# hermesONE_Mini.net
KiCad netlist of a schematic drawn in EAGLE
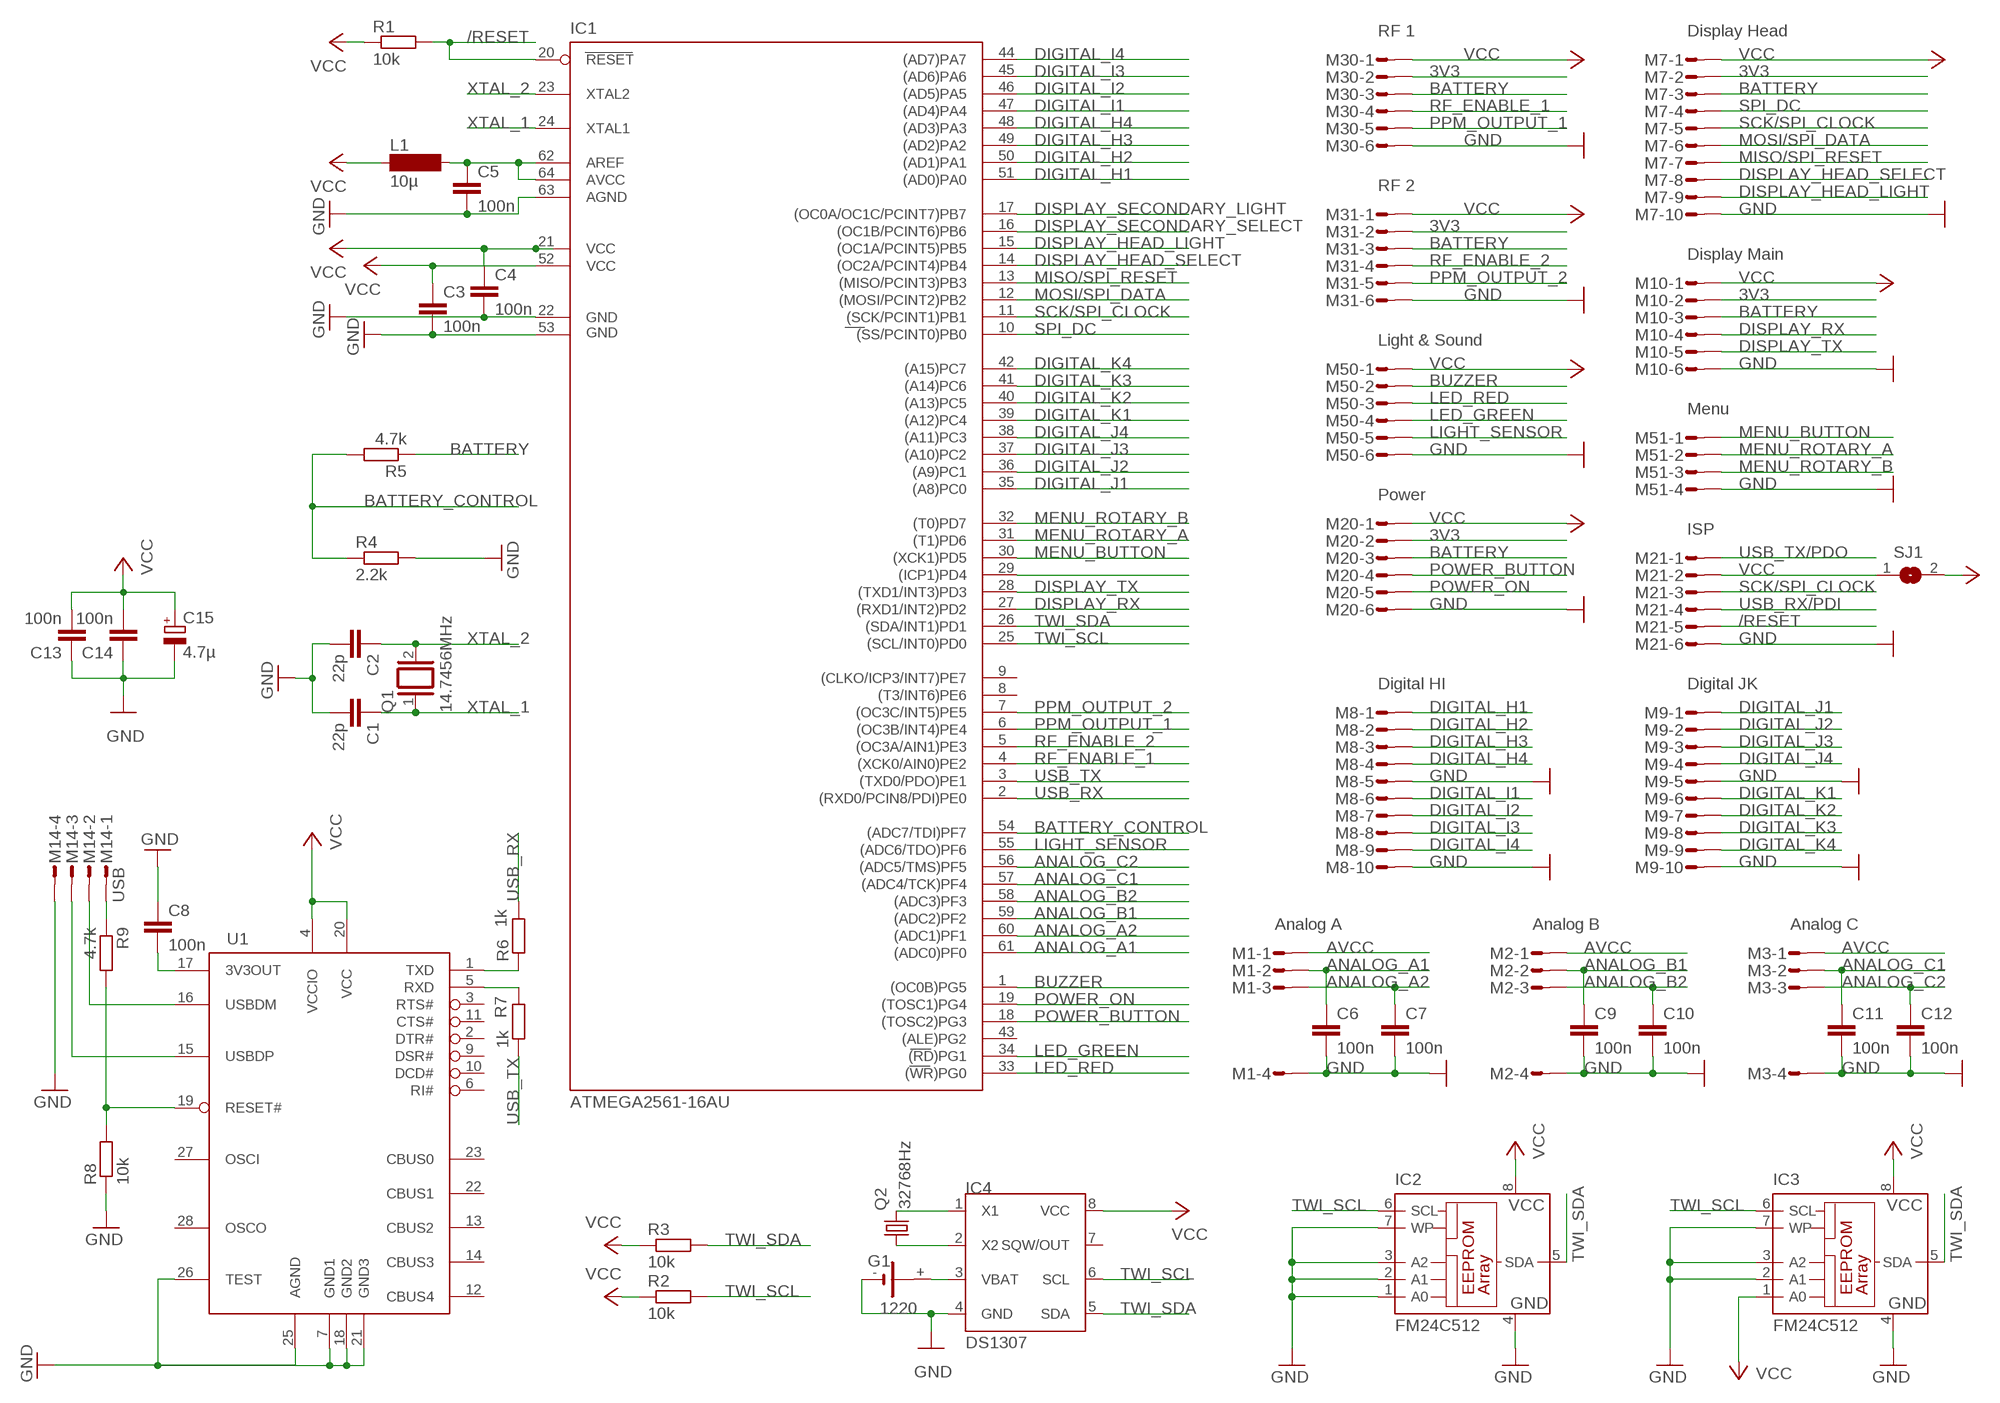
[diagram p0: schematic, sheet 1]

(export (version "E")
  (design (tool "Eeschema 10.0.6"))
  (components
    (comp (ref "C1")
      (value "22p")
      (footprint "eagle-import:C0603")
      (libsource (lib "eagle-import") (part "C-EUC0603"))
    )
    (comp (ref "C2")
      (value "22p")
      (footprint "eagle-import:C0603")
      (libsource (lib "eagle-import") (part "C-EUC0603"))
    )
    (comp (ref "C3")
      (value "100n")
      (footprint "eagle-import:C0603")
      (libsource (lib "eagle-import") (part "C-EUC0603"))
    )
    (comp (ref "C4")
      (value "100n")
      (footprint "eagle-import:C0603")
      (libsource (lib "eagle-import") (part "C-EUC0603"))
    )
    (comp (ref "C5")
      (value "100n")
      (footprint "eagle-import:C0603")
      (libsource (lib "eagle-import") (part "C-EUC0603"))
    )
    (comp (ref "C6")
      (value "100n")
      (footprint "eagle-import:C0603")
      (libsource (lib "eagle-import") (part "C-EUC0603"))
    )
    (comp (ref "C7")
      (value "100n")
      (footprint "eagle-import:C0603")
      (libsource (lib "eagle-import") (part "C-EUC0603"))
    )
    (comp (ref "C8")
      (value "100n")
      (footprint "eagle-import:C0603")
      (libsource (lib "eagle-import") (part "C-EUC0603"))
    )
    (comp (ref "C9")
      (value "100n")
      (footprint "eagle-import:C0603")
      (libsource (lib "eagle-import") (part "C-EUC0603"))
    )
    (comp (ref "C10")
      (value "100n")
      (footprint "eagle-import:C0603")
      (libsource (lib "eagle-import") (part "C-EUC0603"))
    )
    (comp (ref "C11")
      (value "100n")
      (footprint "eagle-import:C0603")
      (libsource (lib "eagle-import") (part "C-EUC0603"))
    )
    (comp (ref "C12")
      (value "100n")
      (footprint "eagle-import:C0603")
      (libsource (lib "eagle-import") (part "C-EUC0603"))
    )
    (comp (ref "C13")
      (value "100n")
      (footprint "eagle-import:C0603")
      (libsource (lib "eagle-import") (part "C-EUC0603"))
    )
    (comp (ref "C14")
      (value "100n")
      (footprint "eagle-import:C0603")
      (libsource (lib "eagle-import") (part "C-EUC0603"))
    )
    (comp (ref "C15")
      (value "4.7µ")
      (footprint "eagle-import:PANASONIC_B")
      (libsource (lib "eagle-import") (part "CPOL-EUB"))
    )
    (comp (ref "G1")
      (value "1220")
      (footprint "eagle-import:KZH12THM")
      (libsource (lib "eagle-import") (part "1220"))
    )
    (comp (ref "IC1")
      (value "ATMEGA2561-16AU")
      (footprint "eagle-import:TQFP64")
      (libsource (lib "eagle-import") (part "ATMEGA2561AU-16"))
    )
    (comp (ref "IC2")
      (value "FM24C512")
      (footprint "eagle-import:SO-08M")
      (libsource (lib "eagle-import") (part "24SMC64"))
    )
    (comp (ref "IC3")
      (value "FM24C512")
      (footprint "eagle-import:SO-08M")
      (libsource (lib "eagle-import") (part "24SMC64"))
    )
    (comp (ref "IC4")
      (value "DS1307")
      (footprint "eagle-import:SOIC-8")
      (libsource (lib "eagle-import") (part "DS1307"))
    )
    (comp (ref "L1")
      (value "10µ")
      (footprint "eagle-import:SM-1206")
      (libsource (lib "eagle-import") (part "SM-1206"))
    )
    (comp (ref "M1")
      (value "Analog A")
      (footprint "eagle-import:MT-4")
      (fields (field (name "MPN") "7-215079-4"))
      (libsource (lib "eagle-import") (part "MT-4"))
    )
    (comp (ref "M2")
      (value "Analog B")
      (footprint "eagle-import:MT-4")
      (fields (field (name "MPN") "7-215079-4"))
      (libsource (lib "eagle-import") (part "MT-4"))
    )
    (comp (ref "M3")
      (value "Analog C")
      (footprint "eagle-import:MT-4")
      (fields (field (name "MPN") "7-215079-4"))
      (libsource (lib "eagle-import") (part "MT-4"))
    )
    (comp (ref "M7")
      (value "Display Head")
      (footprint "eagle-import:MT-10")
      (fields (field (name "MF") "FARNELL") (field (name "MPN") "8-215079-0"))
      (libsource (lib "eagle-import") (part "MT-10"))
    )
    (comp (ref "M8")
      (value "Digital HI")
      (footprint "eagle-import:MT-10")
      (fields (field (name "MF") "FARNELL") (field (name "MPN") "8-215079-0"))
      (libsource (lib "eagle-import") (part "MT-10"))
    )
    (comp (ref "M9")
      (value "Digital JK")
      (footprint "eagle-import:MT-10")
      (fields (field (name "MF") "FARNELL") (field (name "MPN") "8-215079-0"))
      (libsource (lib "eagle-import") (part "MT-10"))
    )
    (comp (ref "M10")
      (value "Display Main")
      (footprint "eagle-import:MT-6")
      (fields (field (name "MPN") "7-215079-6"))
      (libsource (lib "eagle-import") (part "MT-6"))
    )
    (comp (ref "M14")
      (value "USB")
      (footprint "eagle-import:MT-4")
      (fields (field (name "MPN") "7-215079-4"))
      (libsource (lib "eagle-import") (part "MT-4"))
    )
    (comp (ref "M20")
      (value "Power")
      (footprint "eagle-import:MT-6")
      (fields (field (name "MPN") "7-215079-6"))
      (libsource (lib "eagle-import") (part "MT-6"))
    )
    (comp (ref "M21")
      (value "ISP")
      (footprint "eagle-import:MT-6")
      (fields (field (name "MPN") "7-215079-6"))
      (libsource (lib "eagle-import") (part "MT-6"))
    )
    (comp (ref "M30")
      (value "RF 1")
      (footprint "eagle-import:MT-6")
      (fields (field (name "MPN") "7-215079-6"))
      (libsource (lib "eagle-import") (part "MT-6"))
    )
    (comp (ref "M31")
      (value "RF 2")
      (footprint "eagle-import:MT-6")
      (fields (field (name "MPN") "7-215079-6"))
      (libsource (lib "eagle-import") (part "MT-6"))
    )
    (comp (ref "M50")
      (value "Light & Sound")
      (footprint "eagle-import:MT-6")
      (fields (field (name "MPN") "7-215079-6"))
      (libsource (lib "eagle-import") (part "MT-6"))
    )
    (comp (ref "M51")
      (value "Menu")
      (footprint "eagle-import:MT-4")
      (fields (field (name "MPN") "7-215079-4"))
      (libsource (lib "eagle-import") (part "MT-4"))
    )
    (comp (ref "Q1")
      (value "14.7456MHz")
      (footprint "eagle-import:QS")
      (libsource (lib "eagle-import") (part "XTAL/S"))
    )
    (comp (ref "Q2")
      (value "32768Hz")
      (footprint "eagle-import:TC26H")
      (libsource (lib "eagle-import") (part "CRYSTALTC26H"))
    )
    (comp (ref "R1")
      (value "10k")
      (footprint "eagle-import:R0603")
      (libsource (lib "eagle-import") (part "R-EU_R0603"))
    )
    (comp (ref "R2")
      (value "10k")
      (footprint "eagle-import:R0603")
      (libsource (lib "eagle-import") (part "R-EU_R0603"))
    )
    (comp (ref "R3")
      (value "10k")
      (footprint "eagle-import:R0603")
      (libsource (lib "eagle-import") (part "R-EU_R0603"))
    )
    (comp (ref "R4")
      (value "2.2k")
      (footprint "eagle-import:R0603")
      (libsource (lib "eagle-import") (part "R-EU_R0603"))
    )
    (comp (ref "R5")
      (value "4.7k")
      (footprint "eagle-import:R0603")
      (libsource (lib "eagle-import") (part "R-EU_R0603"))
    )
    (comp (ref "R6")
      (value "1k")
      (footprint "eagle-import:R0603")
      (libsource (lib "eagle-import") (part "R-EU_R0603"))
    )
    (comp (ref "R7")
      (value "1k")
      (footprint "eagle-import:R0603")
      (libsource (lib "eagle-import") (part "R-EU_R0603"))
    )
    (comp (ref "R8")
      (value "10k")
      (footprint "eagle-import:R0603")
      (libsource (lib "eagle-import") (part "R-EU_R0603"))
    )
    (comp (ref "R9")
      (value "4.7k")
      (footprint "eagle-import:R0603")
      (libsource (lib "eagle-import") (part "R-EU_R0603"))
    )
    (comp (ref "SJ1") (value "SJ") (footprint "eagle-import:SJ") (libsource (lib "eagle-import") (part "SJ")))
    (comp (ref "U1")
      (value "FT232RL")
      (footprint "eagle-import:SSOP28DB")
      (libsource (lib "eagle-import") (part "FT232RL"))
    )
  )
  (nets
    (net (code "1") (name "/3V3") (class "Default")
      (node (ref "M10") (pin "2") (pinfunction "S_2") (pintype "passive"))
      (node (ref "M20") (pin "2") (pinfunction "S_2") (pintype "passive"))
      (node (ref "M30") (pin "2") (pinfunction "S_2") (pintype "passive"))
      (node (ref "M31") (pin "2") (pinfunction "S_2") (pintype "passive"))
      (node (ref "M7") (pin "2") (pinfunction "S_2") (pintype "passive"))
    )
    (net (code "2") (name "/ANALOG_A1") (class "Default")
      (node (ref "C6") (pin "1") (pinfunction "1_1") (pintype "passive"))
      (node (ref "IC1") (pin "61") (pinfunction "(ADC0)PF0_61") (pintype "bidirectional"))
      (node (ref "M1") (pin "2") (pinfunction "S_2") (pintype "passive"))
    )
    (net (code "3") (name "/ANALOG_A2") (class "Default")
      (node (ref "C7") (pin "1") (pinfunction "1_1") (pintype "passive"))
      (node (ref "IC1") (pin "60") (pinfunction "(ADC1)PF1_60") (pintype "bidirectional"))
      (node (ref "M1") (pin "3") (pinfunction "S_3") (pintype "passive"))
    )
    (net (code "4") (name "/ANALOG_B1") (class "Default")
      (node (ref "C9") (pin "1") (pinfunction "1_1") (pintype "passive"))
      (node (ref "IC1") (pin "59") (pinfunction "(ADC2)PF2_59") (pintype "bidirectional"))
      (node (ref "M2") (pin "2") (pinfunction "S_2") (pintype "passive"))
    )
    (net (code "5") (name "/ANALOG_B2") (class "Default")
      (node (ref "C10") (pin "1") (pinfunction "1_1") (pintype "passive"))
      (node (ref "IC1") (pin "58") (pinfunction "(ADC3)PF3_58") (pintype "bidirectional"))
      (node (ref "M2") (pin "3") (pinfunction "S_3") (pintype "passive"))
    )
    (net (code "6") (name "/ANALOG_C1") (class "Default")
      (node (ref "C11") (pin "1") (pinfunction "1_1") (pintype "passive"))
      (node (ref "IC1") (pin "57") (pinfunction "(ADC4/TCK)PF4_57") (pintype "bidirectional"))
      (node (ref "M3") (pin "2") (pinfunction "S_2") (pintype "passive"))
    )
    (net (code "7") (name "/ANALOG_C2") (class "Default")
      (node (ref "C12") (pin "1") (pinfunction "1_1") (pintype "passive"))
      (node (ref "IC1") (pin "56") (pinfunction "(ADC5/TMS)PF5_56") (pintype "bidirectional"))
      (node (ref "M3") (pin "3") (pinfunction "S_3") (pintype "passive"))
    )
    (net (code "8") (name "/AVCC") (class "Default")
      (node (ref "M1") (pin "1") (pinfunction "S_1") (pintype "passive"))
      (node (ref "M2") (pin "1") (pinfunction "S_1") (pintype "passive"))
      (node (ref "M3") (pin "1") (pinfunction "S_1") (pintype "passive"))
    )
    (net (code "9") (name "/BATTERY") (class "Default")
      (node (ref "M10") (pin "3") (pinfunction "S_3") (pintype "passive"))
      (node (ref "M20") (pin "3") (pinfunction "S_3") (pintype "passive"))
      (node (ref "M30") (pin "3") (pinfunction "S_3") (pintype "passive"))
      (node (ref "M31") (pin "3") (pinfunction "S_3") (pintype "passive"))
      (node (ref "M7") (pin "3") (pinfunction "S_3") (pintype "passive"))
      (node (ref "R5") (pin "1") (pinfunction "1_1") (pintype "passive"))
    )
    (net (code "10") (name "/BATTERY_CONTROL") (class "Default")
      (node (ref "IC1") (pin "54") (pinfunction "(ADC7/TDI)PF7_54") (pintype "bidirectional"))
      (node (ref "R4") (pin "1") (pinfunction "1_1") (pintype "passive"))
      (node (ref "R5") (pin "2") (pinfunction "2_2") (pintype "passive"))
    )
    (net (code "11") (name "/BUZZER") (class "Default")
      (node (ref "IC1") (pin "1") (pinfunction "(OC0B)PG5_1") (pintype "bidirectional"))
      (node (ref "M50") (pin "2") (pinfunction "S_2") (pintype "passive"))
    )
    (net (code "12") (name "/DIGITAL_H1") (class "Default")
      (node (ref "IC1") (pin "51") (pinfunction "(AD0)PA0_51") (pintype "bidirectional"))
      (node (ref "M8") (pin "1") (pinfunction "S_1") (pintype "passive"))
    )
    (net (code "13") (name "/DIGITAL_H2") (class "Default")
      (node (ref "IC1") (pin "50") (pinfunction "(AD1)PA1_50") (pintype "bidirectional"))
      (node (ref "M8") (pin "2") (pinfunction "S_2") (pintype "passive"))
    )
    (net (code "14") (name "/DIGITAL_H3") (class "Default")
      (node (ref "IC1") (pin "49") (pinfunction "(AD2)PA2_49") (pintype "bidirectional"))
      (node (ref "M8") (pin "3") (pinfunction "S_3") (pintype "passive"))
    )
    (net (code "15") (name "/DIGITAL_H4") (class "Default")
      (node (ref "IC1") (pin "48") (pinfunction "(AD3)PA3_48") (pintype "bidirectional"))
      (node (ref "M8") (pin "4") (pinfunction "S_4") (pintype "passive"))
    )
    (net (code "16") (name "/DIGITAL_I1") (class "Default")
      (node (ref "IC1") (pin "47") (pinfunction "(AD4)PA4_47") (pintype "bidirectional"))
      (node (ref "M8") (pin "6") (pinfunction "S_6") (pintype "passive"))
    )
    (net (code "17") (name "/DIGITAL_I2") (class "Default")
      (node (ref "IC1") (pin "46") (pinfunction "(AD5)PA5_46") (pintype "bidirectional"))
      (node (ref "M8") (pin "7") (pinfunction "S_7") (pintype "passive"))
    )
    (net (code "18") (name "/DIGITAL_I3") (class "Default")
      (node (ref "IC1") (pin "45") (pinfunction "(AD6)PA6_45") (pintype "bidirectional"))
      (node (ref "M8") (pin "8") (pinfunction "S_8") (pintype "passive"))
    )
    (net (code "19") (name "/DIGITAL_I4") (class "Default")
      (node (ref "IC1") (pin "44") (pinfunction "(AD7)PA7_44") (pintype "bidirectional"))
      (node (ref "M8") (pin "9") (pinfunction "S_9") (pintype "passive"))
    )
    (net (code "20") (name "/DIGITAL_J1") (class "Default")
      (node (ref "IC1") (pin "35") (pinfunction "(A8)PC0_35") (pintype "bidirectional"))
      (node (ref "M9") (pin "1") (pinfunction "S_1") (pintype "passive"))
    )
    (net (code "21") (name "/DIGITAL_J2") (class "Default")
      (node (ref "IC1") (pin "36") (pinfunction "(A9)PC1_36") (pintype "bidirectional"))
      (node (ref "M9") (pin "2") (pinfunction "S_2") (pintype "passive"))
    )
    (net (code "22") (name "/DIGITAL_J3") (class "Default")
      (node (ref "IC1") (pin "37") (pinfunction "(A10)PC2_37") (pintype "bidirectional"))
      (node (ref "M9") (pin "3") (pinfunction "S_3") (pintype "passive"))
    )
    (net (code "23") (name "/DIGITAL_J4") (class "Default")
      (node (ref "IC1") (pin "38") (pinfunction "(A11)PC3_38") (pintype "bidirectional"))
      (node (ref "M9") (pin "4") (pinfunction "S_4") (pintype "passive"))
    )
    (net (code "24") (name "/DIGITAL_K1") (class "Default")
      (node (ref "IC1") (pin "39") (pinfunction "(A12)PC4_39") (pintype "bidirectional"))
      (node (ref "M9") (pin "6") (pinfunction "S_6") (pintype "passive"))
    )
    (net (code "25") (name "/DIGITAL_K2") (class "Default")
      (node (ref "IC1") (pin "40") (pinfunction "(A13)PC5_40") (pintype "bidirectional"))
      (node (ref "M9") (pin "7") (pinfunction "S_7") (pintype "passive"))
    )
    (net (code "26") (name "/DIGITAL_K3") (class "Default")
      (node (ref "IC1") (pin "41") (pinfunction "(A14)PC6_41") (pintype "bidirectional"))
      (node (ref "M9") (pin "8") (pinfunction "S_8") (pintype "passive"))
    )
    (net (code "27") (name "/DIGITAL_K4") (class "Default")
      (node (ref "IC1") (pin "42") (pinfunction "(A15)PC7_42") (pintype "bidirectional"))
      (node (ref "M9") (pin "9") (pinfunction "S_9") (pintype "passive"))
    )
    (net (code "28") (name "/DISPLAY_HEAD_LIGHT") (class "Default")
      (node (ref "IC1") (pin "15") (pinfunction "(OC1A/PCINT5)PB5_15") (pintype "bidirectional"))
      (node (ref "M7") (pin "9") (pinfunction "S_9") (pintype "passive"))
    )
    (net (code "29") (name "/DISPLAY_HEAD_SELECT") (class "Default")
      (node (ref "IC1") (pin "14") (pinfunction "(OC2A/PCINT4)PB4_14") (pintype "bidirectional"))
      (node (ref "M7") (pin "8") (pinfunction "S_8") (pintype "passive"))
    )
    (net (code "30") (name "/DISPLAY_RX") (class "Default")
      (node (ref "IC1") (pin "27") (pinfunction "(RXD1/INT2)PD2_27") (pintype "bidirectional"))
      (node (ref "M10") (pin "4") (pinfunction "S_4") (pintype "passive"))
    )
    (net (code "31") (name "/DISPLAY_SECONDARY_LIGHT") (class "Default")
      (node (ref "IC1") (pin "17") (pinfunction "(OC0A/OC1C/PCINT7)PB7_17") (pintype "bidirectional"))
    )
    (net (code "32") (name "/DISPLAY_SECONDARY_SELECT") (class "Default")
      (node (ref "IC1") (pin "16") (pinfunction "(OC1B/PCINT6)PB6_16") (pintype "bidirectional"))
    )
    (net (code "33") (name "/DISPLAY_TX") (class "Default")
      (node (ref "IC1") (pin "28") (pinfunction "(TXD1/INT3)PD3_28") (pintype "bidirectional"))
      (node (ref "M10") (pin "5") (pinfunction "S_5") (pintype "passive"))
    )
    (net (code "34") (name "/LED_GREEN") (class "Default")
      (node (ref "IC1") (pin "34") (pinfunction "(RD)PG1_34") (pintype "bidirectional"))
      (node (ref "M50") (pin "4") (pinfunction "S_4") (pintype "passive"))
    )
    (net (code "35") (name "/LED_RED") (class "Default")
      (node (ref "IC1") (pin "33") (pinfunction "(WR)PG0_33") (pintype "bidirectional"))
      (node (ref "M50") (pin "3") (pinfunction "S_3") (pintype "passive"))
    )
    (net (code "36") (name "/LIGHT_SENSOR") (class "Default")
      (node (ref "IC1") (pin "55") (pinfunction "(ADC6/TDO)PF6_55") (pintype "bidirectional"))
      (node (ref "M50") (pin "5") (pinfunction "S_5") (pintype "passive"))
    )
    (net (code "37") (name "/MENU_BUTTON") (class "Default")
      (node (ref "IC1") (pin "30") (pinfunction "(XCK1)PD5_30") (pintype "bidirectional"))
      (node (ref "M51") (pin "1") (pinfunction "S_1") (pintype "passive"))
    )
    (net (code "38") (name "/MENU_ROTARY_A") (class "Default")
      (node (ref "IC1") (pin "31") (pinfunction "(T1)PD6_31") (pintype "bidirectional"))
      (node (ref "M51") (pin "2") (pinfunction "S_2") (pintype "passive"))
    )
    (net (code "39") (name "/MENU_ROTARY_B") (class "Default")
      (node (ref "IC1") (pin "32") (pinfunction "(T0)PD7_32") (pintype "bidirectional"))
      (node (ref "M51") (pin "3") (pinfunction "S_3") (pintype "passive"))
    )
    (net (code "40") (name "/MISO{slash}SPI_RESET") (class "Default")
      (node (ref "IC1") (pin "13") (pinfunction "(MISO/PCINT3)PB3_13") (pintype "bidirectional"))
      (node (ref "M7") (pin "7") (pinfunction "S_7") (pintype "passive"))
    )
    (net (code "41") (name "/MOSI{slash}SPI_DATA") (class "Default")
      (node (ref "IC1") (pin "12") (pinfunction "(MOSI/PCINT2)PB2_12") (pintype "bidirectional"))
      (node (ref "M7") (pin "6") (pinfunction "S_6") (pintype "passive"))
    )
    (net (code "42") (name "/POWER_BUTTON") (class "Default")
      (node (ref "IC1") (pin "18") (pinfunction "(TOSC2)PG3_18") (pintype "bidirectional"))
      (node (ref "M20") (pin "4") (pinfunction "S_4") (pintype "passive"))
    )
    (net (code "43") (name "/POWER_ON") (class "Default")
      (node (ref "IC1") (pin "19") (pinfunction "(TOSC1)PG4_19") (pintype "bidirectional"))
      (node (ref "M20") (pin "5") (pinfunction "S_5") (pintype "passive"))
    )
    (net (code "44") (name "/PPM_OUTPUT_1") (class "Default")
      (node (ref "IC1") (pin "6") (pinfunction "(OC3B/INT4)PE4_6") (pintype "bidirectional"))
      (node (ref "M30") (pin "5") (pinfunction "S_5") (pintype "passive"))
    )
    (net (code "45") (name "/PPM_OUTPUT_2") (class "Default")
      (node (ref "IC1") (pin "7") (pinfunction "(OC3C/INT5)PE5_7") (pintype "bidirectional"))
      (node (ref "M31") (pin "5") (pinfunction "S_5") (pintype "passive"))
    )
    (net (code "46") (name "/RF_ENABLE_1") (class "Default")
      (node (ref "IC1") (pin "4") (pinfunction "(XCK0/AIN0)PE2_4") (pintype "bidirectional"))
      (node (ref "M30") (pin "4") (pinfunction "S_4") (pintype "passive"))
    )
    (net (code "47") (name "/RF_ENABLE_2") (class "Default")
      (node (ref "IC1") (pin "5") (pinfunction "(OC3A/AIN1)PE3_5") (pintype "bidirectional"))
      (node (ref "M31") (pin "4") (pinfunction "S_4") (pintype "passive"))
    )
    (net (code "48") (name "/SCK{slash}SPI_CLOCK") (class "Default")
      (node (ref "IC1") (pin "11") (pinfunction "(SCK/PCINT1)PB1_11") (pintype "bidirectional"))
      (node (ref "M21") (pin "3") (pinfunction "S_3") (pintype "passive"))
      (node (ref "M7") (pin "5") (pinfunction "S_5") (pintype "passive"))
    )
    (net (code "49") (name "/SPI_DC") (class "Default")
      (node (ref "IC1") (pin "10") (pinfunction "(SS/PCINT0)PB0_10") (pintype "bidirectional"))
      (node (ref "M7") (pin "4") (pinfunction "S_4") (pintype "passive"))
    )
    (net (code "50") (name "/TWI_SCL") (class "Default")
      (node (ref "IC1") (pin "25") (pinfunction "(SCL/INT0)PD0_25") (pintype "bidirectional"))
      (node (ref "IC2") (pin "6") (pinfunction "SCL_6") (pintype "input"))
      (node (ref "IC3") (pin "6") (pinfunction "SCL_6") (pintype "input"))
      (node (ref "IC4") (pin "6") (pinfunction "SCL_6") (pintype "input"))
      (node (ref "R2") (pin "2") (pinfunction "2_2") (pintype "passive"))
    )
    (net (code "51") (name "/TWI_SDA") (class "Default")
      (node (ref "IC1") (pin "26") (pinfunction "(SDA/INT1)PD1_26") (pintype "bidirectional"))
      (node (ref "IC2") (pin "5") (pinfunction "SDA_5") (pintype "bidirectional"))
      (node (ref "IC3") (pin "5") (pinfunction "SDA_5") (pintype "bidirectional"))
      (node (ref "IC4") (pin "5") (pinfunction "SDA_5") (pintype "bidirectional"))
      (node (ref "R3") (pin "2") (pinfunction "2_2") (pintype "passive"))
    )
    (net (code "52") (name "/USB_RX") (class "Default")
      (node (ref "IC1") (pin "2") (pinfunction "(RXD0/PCIN8/PDI)PE0_2") (pintype "bidirectional"))
      (node (ref "R6") (pin "2") (pinfunction "2_2") (pintype "passive"))
    )
    (net (code "53") (name "/USB_RX{slash}PDI") (class "Default")
      (node (ref "M21") (pin "4") (pinfunction "S_4") (pintype "passive"))
    )
    (net (code "54") (name "/USB_TX") (class "Default")
      (node (ref "IC1") (pin "3") (pinfunction "(TXD0/PDO)PE1_3") (pintype "bidirectional"))
      (node (ref "R7") (pin "2") (pinfunction "2_2") (pintype "passive"))
    )
    (net (code "55") (name "/USB_TX{slash}PDO") (class "Default")
      (node (ref "M21") (pin "1") (pinfunction "S_1") (pintype "passive"))
    )
    (net (code "56") (name "/XTAL_1") (class "Default")
      (node (ref "C1") (pin "1") (pinfunction "1_1") (pintype "passive"))
      (node (ref "IC1") (pin "24") (pinfunction "XTAL1_24") (pintype "input"))
      (node (ref "Q1") (pin "1") (pinfunction "1_1") (pintype "passive"))
    )
    (net (code "57") (name "/XTAL_2") (class "Default")
      (node (ref "C2") (pin "1") (pinfunction "1_1") (pintype "passive"))
      (node (ref "IC1") (pin "23") (pinfunction "XTAL2_23") (pintype "output"))
      (node (ref "Q1") (pin "2") (pinfunction "2_2") (pintype "passive"))
    )
    (net (code "58") (name "/{slash}RESET") (class "Default")
      (node (ref "IC1") (pin "20") (pinfunction "RESET_20") (pintype "input"))
      (node (ref "M21") (pin "5") (pinfunction "S_5") (pintype "passive"))
      (node (ref "R1") (pin "2") (pinfunction "2_2") (pintype "passive"))
    )
    (net (code "59") (name "GND") (class "Default")
      (node (ref "C1") (pin "2") (pinfunction "2_2") (pintype "passive"))
      (node (ref "C10") (pin "2") (pinfunction "2_2") (pintype "passive"))
      (node (ref "C11") (pin "2") (pinfunction "2_2") (pintype "passive"))
      (node (ref "C12") (pin "2") (pinfunction "2_2") (pintype "passive"))
      (node (ref "C13") (pin "1") (pinfunction "1_1") (pintype "passive"))
      (node (ref "C14") (pin "1") (pinfunction "1_1") (pintype "passive"))
      (node (ref "C15") (pin "-") (pinfunction "-_-") (pintype "passive"))
      (node (ref "C2") (pin "2") (pinfunction "2_2") (pintype "passive"))
      (node (ref "C3") (pin "2") (pinfunction "2_2") (pintype "passive"))
      (node (ref "C4") (pin "2") (pinfunction "2_2") (pintype "passive"))
      (node (ref "C5") (pin "2") (pinfunction "2_2") (pintype "passive"))
      (node (ref "C6") (pin "2") (pinfunction "2_2") (pintype "passive"))
      (node (ref "C7") (pin "2") (pinfunction "2_2") (pintype "passive"))
      (node (ref "C8") (pin "1") (pinfunction "1_1") (pintype "passive"))
      (node (ref "C9") (pin "2") (pinfunction "2_2") (pintype "passive"))
      (node (ref "G1") (pin "-") (pinfunction "-_-") (pintype "passive"))
      (node (ref "IC1") (pin "22") (pinfunction "GND_22") (pintype "power_in"))
      (node (ref "IC1") (pin "53") (pinfunction "GND1_53") (pintype "power_in"))
      (node (ref "IC1") (pin "63") (pinfunction "AGND_63") (pintype "power_in"))
      (node (ref "IC2") (pin "1") (pinfunction "A0_1") (pintype "input"))
      (node (ref "IC2") (pin "2") (pinfunction "A1_2") (pintype "input"))
      (node (ref "IC2") (pin "3") (pinfunction "A2_3") (pintype "input"))
      (node (ref "IC2") (pin "4") (pinfunction "GND_4") (pintype "power_in"))
      (node (ref "IC2") (pin "7") (pinfunction "WP_7") (pintype "input"))
      (node (ref "IC3") (pin "2") (pinfunction "A1_2") (pintype "input"))
      (node (ref "IC3") (pin "3") (pinfunction "A2_3") (pintype "input"))
      (node (ref "IC3") (pin "4") (pinfunction "GND_4") (pintype "power_in"))
      (node (ref "IC3") (pin "7") (pinfunction "WP_7") (pintype "input"))
      (node (ref "IC4") (pin "4") (pinfunction "GND_4") (pintype "power_in"))
      (node (ref "M1") (pin "4") (pinfunction "S_4") (pintype "passive"))
      (node (ref "M10") (pin "6") (pinfunction "S_6") (pintype "passive"))
      (node (ref "M14") (pin "4") (pinfunction "S_4") (pintype "passive"))
      (node (ref "M2") (pin "4") (pinfunction "S_4") (pintype "passive"))
      (node (ref "M20") (pin "6") (pinfunction "S_6") (pintype "passive"))
      (node (ref "M21") (pin "6") (pinfunction "S_6") (pintype "passive"))
      (node (ref "M3") (pin "4") (pinfunction "S_4") (pintype "passive"))
      (node (ref "M30") (pin "6") (pinfunction "S_6") (pintype "passive"))
      (node (ref "M31") (pin "6") (pinfunction "S_6") (pintype "passive"))
      (node (ref "M50") (pin "6") (pinfunction "S_6") (pintype "passive"))
      (node (ref "M51") (pin "4") (pinfunction "S_4") (pintype "passive"))
      (node (ref "M7") (pin "10") (pinfunction "S_10") (pintype "passive"))
      (node (ref "M8") (pin "10") (pinfunction "S_10") (pintype "passive"))
      (node (ref "M8") (pin "5") (pinfunction "S_5") (pintype "passive"))
      (node (ref "M9") (pin "10") (pinfunction "S_10") (pintype "passive"))
      (node (ref "M9") (pin "5") (pinfunction "S_5") (pintype "passive"))
      (node (ref "R4") (pin "2") (pinfunction "2_2") (pintype "passive"))
      (node (ref "R8") (pin "1") (pinfunction "1_1") (pintype "passive"))
      (node (ref "U1") (pin "18") (pinfunction "GND2_18") (pintype "power_in"))
      (node (ref "U1") (pin "21") (pinfunction "GND3_21") (pintype "power_in"))
      (node (ref "U1") (pin "25") (pinfunction "AGND_25") (pintype "power_in"))
      (node (ref "U1") (pin "26") (pinfunction "TEST_26") (pintype "input"))
      (node (ref "U1") (pin "7") (pinfunction "GND1_7") (pintype "power_in"))
    )
    (net (code "60") (name "Net-(IC1-AREF)") (class "Default")
      (node (ref "C5") (pin "1") (pinfunction "1_1") (pintype "passive"))
      (node (ref "IC1") (pin "62") (pinfunction "AREF_62") (pintype "bidirectional"))
      (node (ref "IC1") (pin "64") (pinfunction "AVCC_64") (pintype "power_in"))
      (node (ref "L1") (pin "2") (pinfunction "2_2") (pintype "passive"))
    )
    (net (code "61") (name "Net-(IC4-VBAT)") (class "Default")
      (node (ref "G1") (pin "+") (pinfunction "+_+") (pintype "passive"))
      (node (ref "IC4") (pin "3") (pinfunction "VBAT_3") (pintype "power_in"))
    )
    (net (code "62") (name "Net-(IC4-X1)") (class "Default")
      (node (ref "IC4") (pin "1") (pinfunction "X1_1") (pintype "input"))
      (node (ref "Q2") (pin "2") (pinfunction "2_2") (pintype "passive"))
    )
    (net (code "63") (name "Net-(IC4-X2)") (class "Default")
      (node (ref "IC4") (pin "2") (pinfunction "X2_2") (pintype "output"))
      (node (ref "Q2") (pin "1") (pinfunction "1_1") (pintype "passive"))
    )
    (net (code "64") (name "Net-(M14A-S)") (class "Default")
      (node (ref "M14") (pin "1") (pinfunction "S_1") (pintype "passive"))
      (node (ref "R9") (pin "1") (pinfunction "1_1") (pintype "passive"))
    )
    (net (code "65") (name "Net-(M14B-S)") (class "Default")
      (node (ref "M14") (pin "2") (pinfunction "S_2") (pintype "passive"))
      (node (ref "U1") (pin "16") (pinfunction "USBDM_16") (pintype "bidirectional"))
    )
    (net (code "66") (name "Net-(M14C-S)") (class "Default")
      (node (ref "M14") (pin "3") (pinfunction "S_3") (pintype "passive"))
      (node (ref "U1") (pin "15") (pinfunction "USBDP_15") (pintype "bidirectional"))
    )
    (net (code "67") (name "Net-(M21B-S)") (class "Default")
      (node (ref "M21") (pin "2") (pinfunction "S_2") (pintype "passive"))
      (node (ref "SJ1") (pin "1") (pinfunction "1_1") (pintype "passive"))
    )
    (net (code "68") (name "Net-(U1-3V3OUT)") (class "Default")
      (node (ref "C8") (pin "2") (pinfunction "2_2") (pintype "passive"))
      (node (ref "U1") (pin "17") (pinfunction "3V3OUT_17") (pintype "output"))
    )
    (net (code "69") (name "Net-(U1-RESET#)") (class "Default")
      (node (ref "R8") (pin "2") (pinfunction "2_2") (pintype "passive"))
      (node (ref "R9") (pin "2") (pinfunction "2_2") (pintype "passive"))
      (node (ref "U1") (pin "19") (pinfunction "RESET#_19") (pintype "input"))
    )
    (net (code "70") (name "Net-(U1-RXD)") (class "Default")
      (node (ref "R7") (pin "1") (pinfunction "1_1") (pintype "passive"))
      (node (ref "U1") (pin "5") (pinfunction "RXD_5") (pintype "input"))
    )
    (net (code "71") (name "Net-(U1-TXD)") (class "Default")
      (node (ref "R6") (pin "1") (pinfunction "1_1") (pintype "passive"))
      (node (ref "U1") (pin "1") (pinfunction "TXD_1") (pintype "output"))
    )
    (net (code "72") (name "VCC") (class "Default")
      (node (ref "C13") (pin "2") (pinfunction "2_2") (pintype "passive"))
      (node (ref "C14") (pin "2") (pinfunction "2_2") (pintype "passive"))
      (node (ref "C15") (pin "+") (pinfunction "+_+") (pintype "passive"))
      (node (ref "C3") (pin "1") (pinfunction "1_1") (pintype "passive"))
      (node (ref "C4") (pin "1") (pinfunction "1_1") (pintype "passive"))
      (node (ref "IC1") (pin "21") (pinfunction "VCC_21") (pintype "power_in"))
      (node (ref "IC1") (pin "52") (pinfunction "VCC1_52") (pintype "power_in"))
      (node (ref "IC2") (pin "8") (pinfunction "VCC_8") (pintype "power_in"))
      (node (ref "IC3") (pin "1") (pinfunction "A0_1") (pintype "input"))
      (node (ref "IC3") (pin "8") (pinfunction "VCC_8") (pintype "power_in"))
      (node (ref "IC4") (pin "8") (pinfunction "VCC_8") (pintype "power_in"))
      (node (ref "L1") (pin "1") (pinfunction "1_1") (pintype "passive"))
      (node (ref "M10") (pin "1") (pinfunction "S_1") (pintype "passive"))
      (node (ref "M20") (pin "1") (pinfunction "S_1") (pintype "passive"))
      (node (ref "M30") (pin "1") (pinfunction "S_1") (pintype "passive"))
      (node (ref "M31") (pin "1") (pinfunction "S_1") (pintype "passive"))
      (node (ref "M50") (pin "1") (pinfunction "S_1") (pintype "passive"))
      (node (ref "M7") (pin "1") (pinfunction "S_1") (pintype "passive"))
      (node (ref "R1") (pin "1") (pinfunction "1_1") (pintype "passive"))
      (node (ref "R2") (pin "1") (pinfunction "1_1") (pintype "passive"))
      (node (ref "R3") (pin "1") (pinfunction "1_1") (pintype "passive"))
      (node (ref "SJ1") (pin "2") (pinfunction "2_2") (pintype "passive"))
      (node (ref "U1") (pin "20") (pinfunction "VCC_20") (pintype "power_in"))
      (node (ref "U1") (pin "4") (pinfunction "VCCIO_4") (pintype "power_in"))
    )
    (net (code "73") (name "unconnected-(IC1-(ALE)PG2-Pad43)") (class "Default")
      (node (ref "IC1") (pin "43") (pinfunction "(ALE)PG2_43") (pintype "bidirectional"))
    )
    (net (code "74") (name "unconnected-(IC1-(CLKO{slash}ICP3{slash}INT7)PE7-Pad9)") (class "Default")
      (node (ref "IC1") (pin "9") (pinfunction "(CLKO/ICP3/INT7)PE7_9") (pintype "bidirectional"))
    )
    (net (code "75") (name "unconnected-(IC1-(ICP1)PD4-Pad29)") (class "Default")
      (node (ref "IC1") (pin "29") (pinfunction "(ICP1)PD4_29") (pintype "bidirectional"))
    )
    (net (code "76") (name "unconnected-(IC1-(T3{slash}INT6)PE6-Pad8)") (class "Default")
      (node (ref "IC1") (pin "8") (pinfunction "(T3/INT6)PE6_8") (pintype "bidirectional"))
    )
    (net (code "77") (name "unconnected-(IC4-SQW{slash}OUT-Pad7)") (class "Default")
      (node (ref "IC4") (pin "7") (pinfunction "SQW/OUT_7") (pintype "output"))
    )
    (net (code "78") (name "unconnected-(U1-CBUS0-Pad23)") (class "Default")
      (node (ref "U1") (pin "23") (pinfunction "CBUS0_23") (pintype "bidirectional"))
    )
    (net (code "79") (name "unconnected-(U1-CBUS1-Pad22)") (class "Default")
      (node (ref "U1") (pin "22") (pinfunction "CBUS1_22") (pintype "bidirectional"))
    )
    (net (code "80") (name "unconnected-(U1-CBUS2-Pad13)") (class "Default")
      (node (ref "U1") (pin "13") (pinfunction "CBUS2_13") (pintype "bidirectional"))
    )
    (net (code "81") (name "unconnected-(U1-CBUS3-Pad14)") (class "Default")
      (node (ref "U1") (pin "14") (pinfunction "CBUS3_14") (pintype "bidirectional"))
    )
    (net (code "82") (name "unconnected-(U1-CBUS4-Pad12)") (class "Default")
      (node (ref "U1") (pin "12") (pinfunction "CBUS4_12") (pintype "bidirectional"))
    )
    (net (code "83") (name "unconnected-(U1-CTS#-Pad11)") (class "Default")
      (node (ref "U1") (pin "11") (pinfunction "CTS#_11") (pintype "input"))
    )
    (net (code "84") (name "unconnected-(U1-DCD#-Pad10)") (class "Default")
      (node (ref "U1") (pin "10") (pinfunction "DCD#_10") (pintype "input"))
    )
    (net (code "85") (name "unconnected-(U1-DSR#-Pad9)") (class "Default")
      (node (ref "U1") (pin "9") (pinfunction "DSR#_9") (pintype "input"))
    )
    (net (code "86") (name "unconnected-(U1-DTR#-Pad2)") (class "Default")
      (node (ref "U1") (pin "2") (pinfunction "DTR#_2") (pintype "output"))
    )
    (net (code "87") (name "unconnected-(U1-OSCI-Pad27)") (class "Default")
      (node (ref "U1") (pin "27") (pinfunction "OSCI_27") (pintype "input"))
    )
    (net (code "88") (name "unconnected-(U1-OSCO-Pad28)") (class "Default")
      (node (ref "U1") (pin "28") (pinfunction "OSCO_28") (pintype "output"))
    )
    (net (code "89") (name "unconnected-(U1-RI#-Pad6)") (class "Default")
      (node (ref "U1") (pin "6") (pinfunction "RI#_6") (pintype "input"))
    )
    (net (code "90") (name "unconnected-(U1-RTS#-Pad3)") (class "Default")
      (node (ref "U1") (pin "3") (pinfunction "RTS#_3") (pintype "output"))
    )
  )
)
